# extBoard_sheet4_adc.net
KiCad netlist of a schematic drawn in Altium Designer
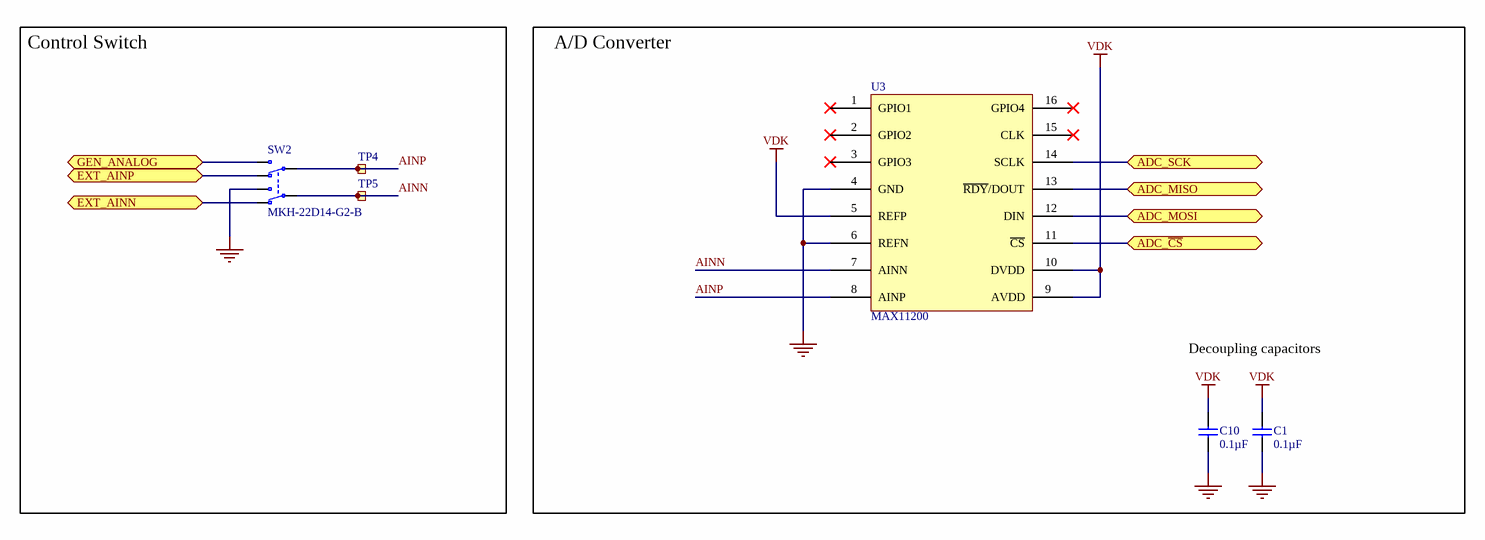
[diagram p0: extBoard_sheet4_adc.SchDoc]

(export (version "E")
  (design (tool "Eeschema 10.0.6"))
  (components
    (comp (ref "C1")
      (value "0.1µF")
      (footprint "CAPC2012X11L")
      (description "Capacitor, X5R, ±10%")
      (fields (field (name "PART NUMBER") "C0805-4µ7") (field (name "PUBLISHER") "Nordic Semiconductor"))
      (libsource (lib "pca10056") (part "CAP_0805"))
    )
    (comp (ref "C10")
      (value "0.1µF")
      (footprint "CAPC2012X11L")
      (description "Capacitor, X5R, ±10%")
      (fields (field (name "PART NUMBER") "C0805-4µ7") (field (name "PUBLISHER") "Nordic Semiconductor"))
      (libsource (lib "pca10056") (part "CAP_0805"))
    )
    (comp (ref "SW2")
      (value "MKH-22D14-G2-B")
      (footprint "MKH-22D14-G2-B")
      (description "Slide Switch DPDT")
      (fields (field (name "MANUFACTURER") "Dailywell") (field (name "PUBLISHER") "Nordic Semiconductor"))
      (libsource (lib "pca10056") (part "MKH-22D14-G2-B"))
    )
    (comp (ref "TP4")
      (value "TP")
      (footprint "TESTPAD-TH")
      (description "Testpoint, through hole")
      (fields (field (name "PART NUMBER") "Testpoint TH") (field (name "PUBLISHER") "Nordic Semiconductor"))
      (libsource (lib "pca10056") (part "Testpoint TH"))
    )
    (comp (ref "TP5")
      (value "TP")
      (footprint "TESTPAD-TH")
      (description "Testpoint, through hole")
      (fields (field (name "PART NUMBER") "Testpoint TH") (field (name "PUBLISHER") "Nordic Semiconductor"))
      (libsource (lib "pca10056") (part "Testpoint TH"))
    )
    (comp (ref "U3")
      (value "MAX11200")
      (footprint "QSOP16")
      (libsource (lib "extBoardLib") (part "MAX11200"))
    )
  )
  (nets
    (net (code "1") (name "/ADC_MISO") (class "Default")
      (node (ref "U3") (pin "13") (pinfunction "~{RDY}/DOUT_13") (pintype "passive"))
    )
    (net (code "2") (name "/ADC_MOSI") (class "Default")
      (node (ref "U3") (pin "12") (pinfunction "DIN_12") (pintype "passive"))
    )
    (net (code "3") (name "/ADC_SCK") (class "Default")
      (node (ref "U3") (pin "14") (pinfunction "SCLK_14") (pintype "passive"))
    )
    (net (code "4") (name "/ADC_~{CS}") (class "Default")
      (node (ref "U3") (pin "11") (pinfunction "~{CS}_11") (pintype "passive"))
    )
    (net (code "5") (name "/AINN") (class "Default")
      (node (ref "SW2") (pin "2") (pinfunction "COM-1_2") (pintype "passive"))
      (node (ref "TP5") (pin "1") (pinfunction "1_1") (pintype "passive"))
      (node (ref "U3") (pin "7") (pinfunction "AINN_7") (pintype "passive"))
    )
    (net (code "6") (name "/AINP") (class "Default")
      (node (ref "SW2") (pin "5") (pinfunction "COM-2_5") (pintype "passive"))
      (node (ref "TP4") (pin "1") (pinfunction "1_1") (pintype "passive"))
      (node (ref "U3") (pin "8") (pinfunction "AINP_8") (pintype "passive"))
    )
    (net (code "7") (name "/EXT_AINN") (class "Default")
      (node (ref "SW2") (pin "3") (pinfunction "N.C-1_3") (pintype "passive"))
    )
    (net (code "8") (name "/EXT_AINP") (class "Default")
      (node (ref "SW2") (pin "6") (pinfunction "N.C-2_6") (pintype "passive"))
    )
    (net (code "9") (name "/GEN_ANALOG") (class "Default")
      (node (ref "SW2") (pin "4") (pinfunction "N.O-2_4") (pintype "passive"))
    )
    (net (code "10") (name "GND") (class "Default")
      (node (ref "C1") (pin "1") (pinfunction "1_1") (pintype "passive"))
      (node (ref "C10") (pin "1") (pinfunction "1_1") (pintype "passive"))
      (node (ref "SW2") (pin "1") (pinfunction "N.O-1_1") (pintype "passive"))
      (node (ref "U3") (pin "4") (pinfunction "GND_4") (pintype "passive"))
      (node (ref "U3") (pin "6") (pinfunction "REFN_6") (pintype "passive"))
    )
    (net (code "11") (name "VDK") (class "Default")
      (node (ref "C1") (pin "2") (pinfunction "2_2") (pintype "passive"))
      (node (ref "C10") (pin "2") (pinfunction "2_2") (pintype "passive"))
      (node (ref "U3") (pin "10") (pinfunction "DVDD_10") (pintype "passive"))
      (node (ref "U3") (pin "5") (pinfunction "REFP_5") (pintype "passive"))
      (node (ref "U3") (pin "9") (pinfunction "AVDD_9") (pintype "passive"))
    )
    (net (code "12") (name "unconnected-(U3-CLK-Pad15)") (class "Default")
      (node (ref "U3") (pin "15") (pinfunction "CLK_15") (pintype "passive+no_connect"))
    )
    (net (code "13") (name "unconnected-(U3-GPIO1-Pad1)") (class "Default")
      (node (ref "U3") (pin "1") (pinfunction "GPIO1_1") (pintype "passive+no_connect"))
    )
    (net (code "14") (name "unconnected-(U3-GPIO2-Pad2)") (class "Default")
      (node (ref "U3") (pin "2") (pinfunction "GPIO2_2") (pintype "passive+no_connect"))
    )
    (net (code "15") (name "unconnected-(U3-GPIO3-Pad3)") (class "Default")
      (node (ref "U3") (pin "3") (pinfunction "GPIO3_3") (pintype "passive+no_connect"))
    )
    (net (code "16") (name "unconnected-(U3-GPIO4-Pad16)") (class "Default")
      (node (ref "U3") (pin "16") (pinfunction "GPIO4_16") (pintype "passive+no_connect"))
    )
  )
)
